# flipdot.net
KiCad netlist of a schematic drawn in Altium Designer
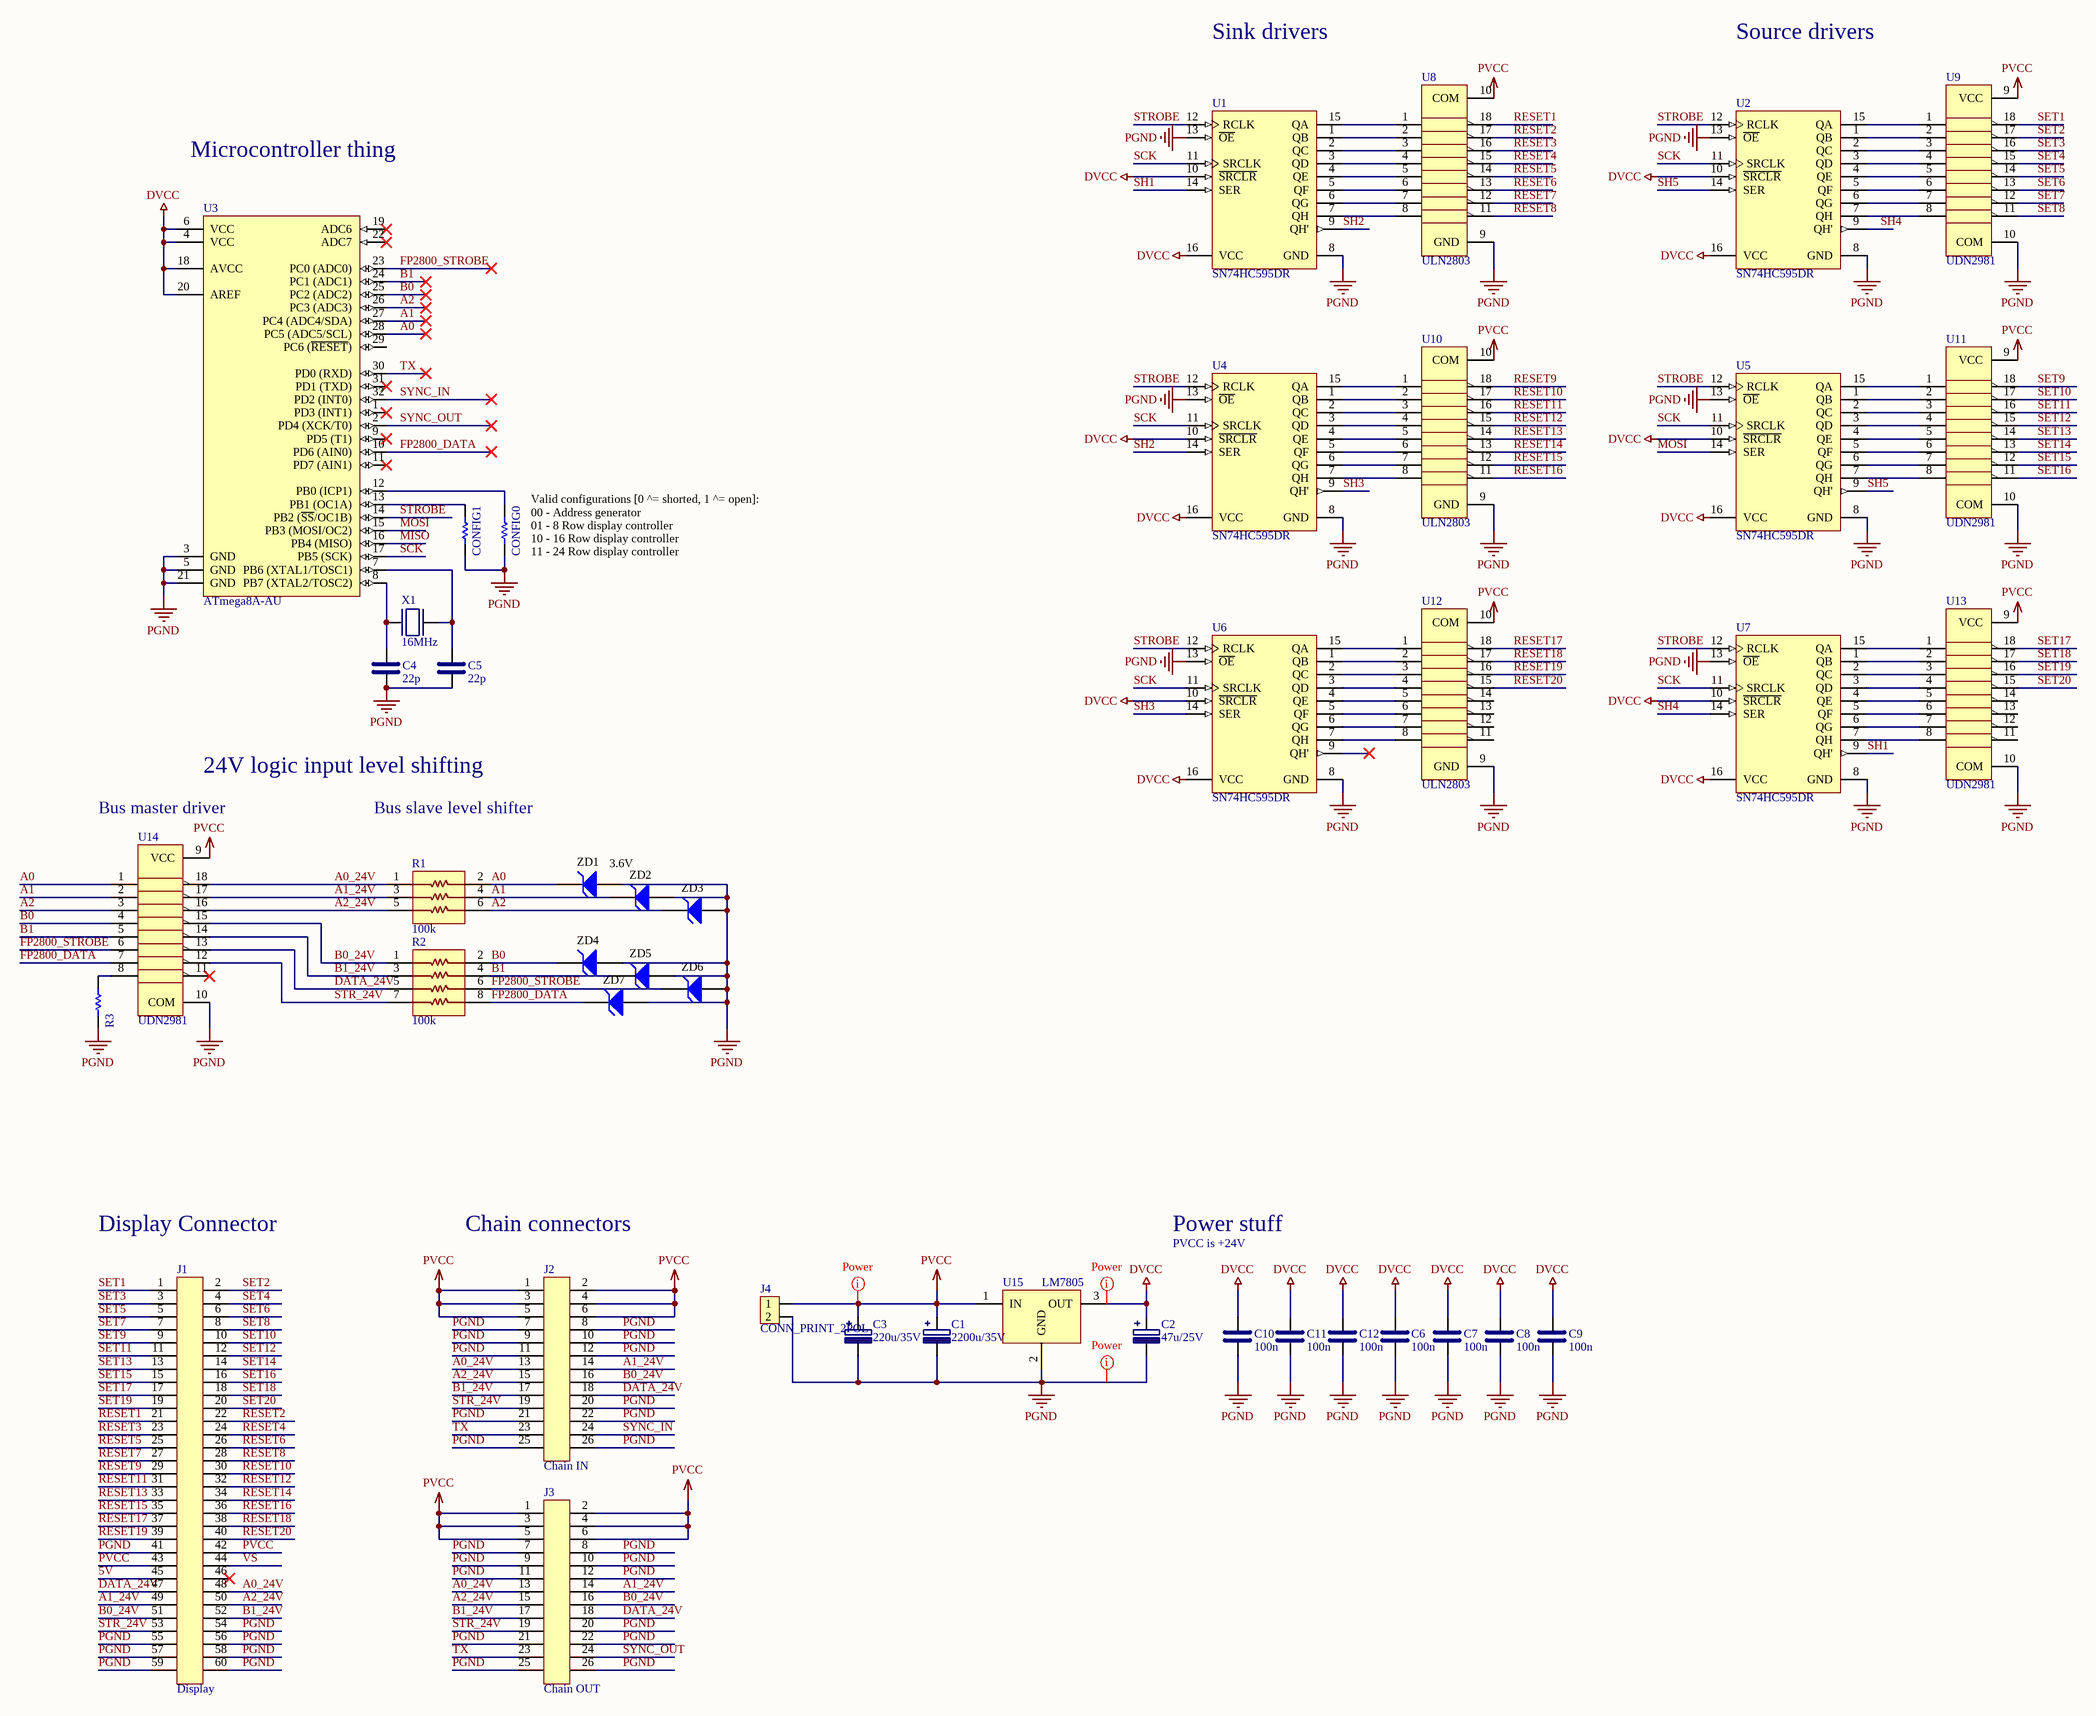
[diagram p0: flipdot.SchDoc]

(export (version "E")
  (design (tool "Eeschema 10.0.6"))
  (components
    (comp (ref "C1")
      (value "2200u/35V")
      (footprint "ELKO_RAD_SIDE_RM7.5_16x25")
      (description "Electrolytic Capacitor")
      (libsource (lib "flipdot") (part "CP"))
    )
    (comp (ref "C2")
      (value "47u/25V")
      (footprint "ELKO_RAD_RM2.0_dia5.0")
      (description "Electrolytic Capacitor")
      (libsource (lib "flipdot") (part "CP"))
    )
    (comp (ref "C3")
      (value "220u/35V")
      (footprint "ELKO_RAD_RM3.5_dia8.0")
      (description "Electrolytic Capacitor")
      (libsource (lib "flipdot") (part "CP"))
    )
    (comp (ref "C4")
      (value "22p")
      (footprint "6-0805_M")
      (description "Ceramic Capacitor")
      (libsource (lib "flipdot") (part "CCer"))
    )
    (comp (ref "C5")
      (value "22p")
      (footprint "6-0805_M")
      (description "Ceramic Capacitor")
      (libsource (lib "flipdot") (part "CCer"))
    )
    (comp (ref "C6")
      (value "100n")
      (footprint "6-0805_M")
      (description "Ceramic Capacitor")
      (libsource (lib "flipdot") (part "CCer"))
    )
    (comp (ref "C7")
      (value "100n")
      (footprint "6-0805_M")
      (description "Ceramic Capacitor")
      (libsource (lib "flipdot") (part "CCer"))
    )
    (comp (ref "C8")
      (value "100n")
      (footprint "6-0805_M")
      (description "Ceramic Capacitor")
      (libsource (lib "flipdot") (part "CCer"))
    )
    (comp (ref "C9")
      (value "100n")
      (footprint "6-0805_M")
      (description "Ceramic Capacitor")
      (libsource (lib "flipdot") (part "CCer"))
    )
    (comp (ref "C10")
      (value "100n")
      (footprint "6-0805_M")
      (description "Ceramic Capacitor")
      (libsource (lib "flipdot") (part "CCer"))
    )
    (comp (ref "C11")
      (value "100n")
      (footprint "6-0805_M")
      (description "Ceramic Capacitor")
      (libsource (lib "flipdot") (part "CCer"))
    )
    (comp (ref "C12")
      (value "100n")
      (footprint "6-0805_M")
      (description "Ceramic Capacitor")
      (libsource (lib "flipdot") (part "CCer"))
    )
    (comp (ref "CONFIG0")
      (value "Jumper 0603(1608)")
      (footprint "RESC0603(1608)_N")
      (description "Jumper 0603 (1608 Metric)")
      (fields (field (name "POWER") "None"))
      (libsource (lib "Altium Content Vault") (part "RES"))
    )
    (comp (ref "CONFIG1")
      (value "Jumper 0603(1608)")
      (footprint "RESC0603(1608)_N")
      (description "Jumper 0603 (1608 Metric)")
      (fields (field (name "POWER") "None"))
      (libsource (lib "Altium Content Vault") (part "RES"))
    )
    (comp (ref "J1")
      (value "Display")
      (footprint "PINHD_2x30_100mil")
      (libsource (lib "flipdot") (part "PINHD_2x30"))
    )
    (comp (ref "J2")
      (value "Chain IN")
      (footprint "PINHD_2x13_100mil")
      (libsource (lib "flipdot") (part "PINHD_2x13"))
    )
    (comp (ref "J3")
      (value "Chain OUT")
      (footprint "PINHD_2x13_100mil")
      (libsource (lib "flipdot") (part "PINHD_2x13"))
    )
    (comp (ref "J4")
      (value "CONN_PRINT_2POL")
      (footprint "CONN_PLUG_2P_5.08")
      (libsource (lib "flipdot") (part "CONN_PRINT_2POL"))
    )
    (comp (ref "R1")
      (value "100k")
      (footprint "RNET_SIL_100mil_6P")
      (description "6-pin Parallel Resistor Network")
      (libsource (lib "flipdot") (part "Rnet_Parallel_6"))
    )
    (comp (ref "R2")
      (value "100k")
      (footprint "RNET_SIL_100mil_8P")
      (description "8-pin Parallel Resistor Network")
      (libsource (lib "flipdot") (part "Rnet_Parallel_8"))
    )
    (comp (ref "R3")
      (value "Jumper 0603(1608)")
      (footprint "RESC0603(1608)_N")
      (description "Jumper 0603 (1608 Metric)")
      (fields (field (name "POWER") "None"))
      (libsource (lib "Altium Content Vault") (part "RES"))
    )
    (comp (ref "U1")
      (value "SN74HC595DR")
      (footprint "D0016A_M")
      (description "8-Bit Shift Registers With 3-State Output Registers, D0016A, LARGE T&R")
      (fields
        (field (name "GENERIC PART NUMBER") "SN74HC595")
        (field (name "MANUFACTURER") "Texas Instruments")
      )
      (libsource (lib "Altium Content Vault") (part "CMP-0780-00037-3"))
    )
    (comp (ref "U2")
      (value "SN74HC595DR")
      (footprint "D0016A_M")
      (description "8-Bit Shift Registers With 3-State Output Registers, D0016A, LARGE T&R")
      (fields
        (field (name "GENERIC PART NUMBER") "SN74HC595")
        (field (name "MANUFACTURER") "Texas Instruments")
      )
      (libsource (lib "Altium Content Vault") (part "CMP-0780-00037-3"))
    )
    (comp (ref "U3")
      (value "ATmega8A-AU")
      (footprint "32A_M")
      (libsource (lib "Altium Content Vault") (part "MC-8B-ATM8-SQ32"))
    )
    (comp (ref "U4")
      (value "SN74HC595DR")
      (footprint "D0016A_M")
      (description "8-Bit Shift Registers With 3-State Output Registers, D0016A, LARGE T&R")
      (fields
        (field (name "GENERIC PART NUMBER") "SN74HC595")
        (field (name "MANUFACTURER") "Texas Instruments")
      )
      (libsource (lib "Altium Content Vault") (part "CMP-0780-00037-3"))
    )
    (comp (ref "U5")
      (value "SN74HC595DR")
      (footprint "D0016A_M")
      (description "8-Bit Shift Registers With 3-State Output Registers, D0016A, LARGE T&R")
      (fields
        (field (name "GENERIC PART NUMBER") "SN74HC595")
        (field (name "MANUFACTURER") "Texas Instruments")
      )
      (libsource (lib "Altium Content Vault") (part "CMP-0780-00037-3"))
    )
    (comp (ref "U6")
      (value "SN74HC595DR")
      (footprint "D0016A_M")
      (description "8-Bit Shift Registers With 3-State Output Registers, D0016A, LARGE T&R")
      (fields
        (field (name "GENERIC PART NUMBER") "SN74HC595")
        (field (name "MANUFACTURER") "Texas Instruments")
      )
      (libsource (lib "Altium Content Vault") (part "CMP-0780-00037-3"))
    )
    (comp (ref "U7")
      (value "SN74HC595DR")
      (footprint "D0016A_M")
      (description "8-Bit Shift Registers With 3-State Output Registers, D0016A, LARGE T&R")
      (fields
        (field (name "GENERIC PART NUMBER") "SN74HC595")
        (field (name "MANUFACTURER") "Texas Instruments")
      )
      (libsource (lib "Altium Content Vault") (part "CMP-0780-00037-3"))
    )
    (comp (ref "U8")
      (value "ULN2803")
      (footprint "PDIP-18")
      (description "ULN2803 Octal Darlington Sink Driver")
      (libsource (lib "flipdot") (part "ULN2803"))
    )
    (comp (ref "U9")
      (value "UDN2981")
      (footprint "PDIP-18")
      (description "UDN2981 Octal Darlington Source Driver/Level Shifter")
      (libsource (lib "flipdot") (part "UDN2981"))
    )
    (comp (ref "U10")
      (value "ULN2803")
      (footprint "PDIP-18")
      (description "ULN2803 Octal Darlington Sink Driver")
      (libsource (lib "flipdot") (part "ULN2803"))
    )
    (comp (ref "U11")
      (value "UDN2981")
      (footprint "PDIP-18")
      (description "UDN2981 Octal Darlington Source Driver/Level Shifter")
      (libsource (lib "flipdot") (part "UDN2981"))
    )
    (comp (ref "U12")
      (value "ULN2803")
      (footprint "PDIP-18")
      (description "ULN2803 Octal Darlington Sink Driver")
      (libsource (lib "flipdot") (part "ULN2803"))
    )
    (comp (ref "U13")
      (value "UDN2981")
      (footprint "PDIP-18")
      (description "UDN2981 Octal Darlington Source Driver/Level Shifter")
      (libsource (lib "flipdot") (part "UDN2981"))
    )
    (comp (ref "U14")
      (value "UDN2981")
      (footprint "PDIP-18")
      (description "UDN2981 Octal Darlington Source Driver/Level Shifter")
      (libsource (lib "flipdot") (part "UDN2981"))
    )
    (comp (ref "U15")
      (value "LM7805")
      (footprint "TO92")
      (description "5V Linear Regulator")
      (libsource (lib "flipdot") (part "LM7805"))
    )
    (comp (ref "X1") (value "16MHz") (footprint "XTAL-HC49") (libsource (lib "flipdot") (part "XTAL")))
    (comp (ref "ZD1")
      (value "3.6V")
      (footprint "FAIR-DO-41-2_V")
      (description "Zener Diode, 5.6V, 1W, 5%, -65 to 200 degC, 2-Pin DO-41, Body 2.72 x 5.2 mm, RoHS")
      (fields (field (name "MANUFACTURER") "Fairchild Semiconductor") (field (name "TOLERANCE") "5%"))
      (libsource (lib "Altium Content Vault") (part "FAIR-DZEN-A1K2-2"))
    )
    (comp (ref "ZD2")
      (value "3.6V")
      (footprint "FAIR-DO-41-2_V")
      (description "Zener Diode, 5.6V, 1W, 5%, -65 to 200 degC, 2-Pin DO-41, Body 2.72 x 5.2 mm, RoHS")
      (fields (field (name "MANUFACTURER") "Fairchild Semiconductor") (field (name "TOLERANCE") "5%"))
      (libsource (lib "Altium Content Vault") (part "CMP-0892-00009-1"))
    )
    (comp (ref "ZD3")
      (value "3.6V")
      (footprint "FAIR-DO-41-2_V")
      (description "Zener Diode, 5.6V, 1W, 5%, -65 to 200 degC, 2-Pin DO-41, Body 2.72 x 5.2 mm, RoHS")
      (fields (field (name "MANUFACTURER") "Fairchild Semiconductor") (field (name "TOLERANCE") "5%"))
      (libsource (lib "Altium Content Vault") (part "CMP-0892-00009-1"))
    )
    (comp (ref "ZD4")
      (value "3.6V")
      (footprint "FAIR-DO-41-2_V")
      (description "Zener Diode, 5.6V, 1W, 5%, -65 to 200 degC, 2-Pin DO-41, Body 2.72 x 5.2 mm, RoHS")
      (fields (field (name "MANUFACTURER") "Fairchild Semiconductor") (field (name "TOLERANCE") "5%"))
      (libsource (lib "Altium Content Vault") (part "CMP-0892-00009-1"))
    )
    (comp (ref "ZD5")
      (value "3.6V")
      (footprint "FAIR-DO-41-2_V")
      (description "Zener Diode, 5.6V, 1W, 5%, -65 to 200 degC, 2-Pin DO-41, Body 2.72 x 5.2 mm, RoHS")
      (fields (field (name "MANUFACTURER") "Fairchild Semiconductor") (field (name "TOLERANCE") "5%"))
      (libsource (lib "Altium Content Vault") (part "CMP-0892-00009-1"))
    )
    (comp (ref "ZD6")
      (value "3.6V")
      (footprint "FAIR-DO-41-2_V")
      (description "Zener Diode, 5.6V, 1W, 5%, -65 to 200 degC, 2-Pin DO-41, Body 2.72 x 5.2 mm, RoHS")
      (fields (field (name "MANUFACTURER") "Fairchild Semiconductor") (field (name "TOLERANCE") "5%"))
      (libsource (lib "Altium Content Vault") (part "CMP-0892-00009-1"))
    )
    (comp (ref "ZD7")
      (value "3.6V")
      (footprint "FAIR-DO-41-2_V")
      (description "Zener Diode, 5.6V, 1W, 5%, -65 to 200 degC, 2-Pin DO-41, Body 2.72 x 5.2 mm, RoHS")
      (fields (field (name "MANUFACTURER") "Fairchild Semiconductor") (field (name "TOLERANCE") "5%"))
      (libsource (lib "Altium Content Vault") (part "CMP-0892-00009-1"))
    )
  )
  (nets
    (net (code "1") (name "/5V") (class "Default")
      (node (ref "J1") (pin "45") (pinfunction "45_45") (pintype "power_in"))
    )
    (net (code "2") (name "/A0") (class "Default")
      (node (ref "R1") (pin "2") (pintype "power_in"))
      (node (ref "U14") (pin "1") (pinfunction "IN1_1") (pintype "passive"))
      (node (ref "U3") (pin "28") (pinfunction "PC5_(ADC5/SCL)_28") (pintype "bidirectional"))
      (node (ref "ZD1") (pin "2") (pinfunction "K_2") (pintype "passive"))
    )
    (net (code "3") (name "/A0_24V") (class "Default")
      (node (ref "J1") (pin "48") (pinfunction "48_48") (pintype "power_in"))
      (node (ref "J2") (pin "13") (pinfunction "13_13") (pintype "power_in"))
      (node (ref "J3") (pin "13") (pinfunction "13_13") (pintype "power_in"))
      (node (ref "R1") (pin "1") (pinfunction "COM_1") (pintype "power_in"))
      (node (ref "U14") (pin "18") (pinfunction "OUT1_18") (pintype "passive"))
    )
    (net (code "4") (name "/A1") (class "Default")
      (node (ref "R1") (pin "4") (pintype "power_in"))
      (node (ref "U14") (pin "2") (pinfunction "IN2_2") (pintype "passive"))
      (node (ref "U3") (pin "27") (pinfunction "PC4_(ADC4/SDA)_27") (pintype "bidirectional"))
      (node (ref "ZD2") (pin "2") (pinfunction "K_2") (pintype "passive"))
    )
    (net (code "5") (name "/A1_24V") (class "Default")
      (node (ref "J1") (pin "49") (pinfunction "49_49") (pintype "power_in"))
      (node (ref "J2") (pin "14") (pinfunction "14_14") (pintype "power_in"))
      (node (ref "J3") (pin "14") (pinfunction "14_14") (pintype "power_in"))
      (node (ref "R1") (pin "3") (pintype "power_in"))
      (node (ref "U14") (pin "17") (pinfunction "OUT2_17") (pintype "passive"))
    )
    (net (code "6") (name "/A2") (class "Default")
      (node (ref "R1") (pin "6") (pintype "power_in"))
      (node (ref "U14") (pin "3") (pinfunction "IN3_3") (pintype "passive"))
      (node (ref "U3") (pin "26") (pinfunction "PC3_(ADC3)_26") (pintype "bidirectional"))
      (node (ref "ZD3") (pin "2") (pinfunction "K_2") (pintype "passive"))
    )
    (net (code "7") (name "/A2_24V") (class "Default")
      (node (ref "J1") (pin "50") (pinfunction "50_50") (pintype "power_in"))
      (node (ref "J2") (pin "15") (pinfunction "15_15") (pintype "power_in"))
      (node (ref "J3") (pin "15") (pinfunction "15_15") (pintype "power_in"))
      (node (ref "R1") (pin "5") (pintype "power_in"))
      (node (ref "U14") (pin "16") (pinfunction "OUT3_16") (pintype "passive"))
    )
    (net (code "8") (name "/B0") (class "Default")
      (node (ref "R2") (pin "2") (pintype "power_in"))
      (node (ref "U14") (pin "4") (pinfunction "IN4_4") (pintype "passive"))
      (node (ref "U3") (pin "25") (pinfunction "PC2_(ADC2)_25") (pintype "bidirectional"))
      (node (ref "ZD4") (pin "2") (pinfunction "K_2") (pintype "passive"))
    )
    (net (code "9") (name "/B0_24V") (class "Default")
      (node (ref "J1") (pin "51") (pinfunction "51_51") (pintype "power_in"))
      (node (ref "J2") (pin "16") (pinfunction "16_16") (pintype "power_in"))
      (node (ref "J3") (pin "16") (pinfunction "16_16") (pintype "power_in"))
      (node (ref "R2") (pin "1") (pinfunction "COM_1") (pintype "power_in"))
      (node (ref "U14") (pin "15") (pinfunction "OUT4_15") (pintype "passive"))
    )
    (net (code "10") (name "/B1") (class "Default")
      (node (ref "R2") (pin "4") (pintype "power_in"))
      (node (ref "U14") (pin "5") (pinfunction "IN5_5") (pintype "passive"))
      (node (ref "U3") (pin "24") (pinfunction "PC1_(ADC1)_24") (pintype "bidirectional"))
      (node (ref "ZD5") (pin "2") (pinfunction "K_2") (pintype "passive"))
    )
    (net (code "11") (name "/B1_24V") (class "Default")
      (node (ref "J1") (pin "52") (pinfunction "52_52") (pintype "power_in"))
      (node (ref "J2") (pin "17") (pinfunction "17_17") (pintype "power_in"))
      (node (ref "J3") (pin "17") (pinfunction "17_17") (pintype "power_in"))
      (node (ref "R2") (pin "3") (pintype "power_in"))
      (node (ref "U14") (pin "14") (pinfunction "OUT5_14") (pintype "passive"))
    )
    (net (code "12") (name "/DATA_24V") (class "Default")
      (node (ref "J1") (pin "47") (pinfunction "47_47") (pintype "power_in"))
      (node (ref "J2") (pin "18") (pinfunction "18_18") (pintype "power_in"))
      (node (ref "J3") (pin "18") (pinfunction "18_18") (pintype "power_in"))
      (node (ref "R2") (pin "5") (pintype "power_in"))
      (node (ref "U14") (pin "13") (pinfunction "OUT6_13") (pintype "passive"))
    )
    (net (code "13") (name "/FP2800_DATA") (class "Default")
      (node (ref "R2") (pin "8") (pintype "power_in"))
      (node (ref "U14") (pin "7") (pinfunction "IN7_7") (pintype "passive"))
      (node (ref "U3") (pin "10") (pinfunction "PD6_(AIN0)_10") (pintype "bidirectional"))
      (node (ref "ZD7") (pin "2") (pinfunction "K_2") (pintype "passive"))
    )
    (net (code "14") (name "/FP2800_STROBE") (class "Default")
      (node (ref "R2") (pin "6") (pintype "power_in"))
      (node (ref "U14") (pin "6") (pinfunction "IN6_6") (pintype "passive"))
      (node (ref "U3") (pin "23") (pinfunction "PC0_(ADC0)_23") (pintype "bidirectional"))
      (node (ref "ZD6") (pin "2") (pinfunction "K_2") (pintype "passive"))
    )
    (net (code "15") (name "/MISO") (class "Default")
      (node (ref "U3") (pin "16") (pinfunction "PB4_(MISO)_16") (pintype "bidirectional"))
    )
    (net (code "16") (name "/MOSI") (class "Default")
      (node (ref "U3") (pin "15") (pinfunction "PB3_(MOSI/OC2)_15") (pintype "bidirectional"))
      (node (ref "U5") (pin "14") (pinfunction "SER_14") (pintype "input"))
    )
    (net (code "17") (name "/RESET1") (class "Default")
      (node (ref "J1") (pin "21") (pinfunction "21_21") (pintype "power_in"))
      (node (ref "U8") (pin "18") (pinfunction "OUT1_18") (pintype "passive"))
    )
    (net (code "18") (name "/RESET2") (class "Default")
      (node (ref "J1") (pin "22") (pinfunction "22_22") (pintype "power_in"))
      (node (ref "U8") (pin "17") (pinfunction "OUT2_17") (pintype "passive"))
    )
    (net (code "19") (name "/RESET3") (class "Default")
      (node (ref "J1") (pin "23") (pinfunction "23_23") (pintype "power_in"))
      (node (ref "U8") (pin "16") (pinfunction "OUT3_16") (pintype "passive"))
    )
    (net (code "20") (name "/RESET4") (class "Default")
      (node (ref "J1") (pin "24") (pinfunction "24_24") (pintype "power_in"))
      (node (ref "U8") (pin "15") (pinfunction "OUT4_15") (pintype "passive"))
    )
    (net (code "21") (name "/RESET5") (class "Default")
      (node (ref "J1") (pin "25") (pinfunction "25_25") (pintype "power_in"))
      (node (ref "U8") (pin "14") (pinfunction "OUT5_14") (pintype "passive"))
    )
    (net (code "22") (name "/RESET6") (class "Default")
      (node (ref "J1") (pin "26") (pinfunction "26_26") (pintype "power_in"))
      (node (ref "U8") (pin "13") (pinfunction "OUT6_13") (pintype "passive"))
    )
    (net (code "23") (name "/RESET7") (class "Default")
      (node (ref "J1") (pin "27") (pinfunction "27_27") (pintype "power_in"))
      (node (ref "U8") (pin "12") (pinfunction "OUT7_12") (pintype "passive"))
    )
    (net (code "24") (name "/RESET8") (class "Default")
      (node (ref "J1") (pin "28") (pinfunction "28_28") (pintype "power_in"))
      (node (ref "U8") (pin "11") (pinfunction "OUT8_11") (pintype "passive"))
    )
    (net (code "25") (name "/RESET9") (class "Default")
      (node (ref "J1") (pin "29") (pinfunction "29_29") (pintype "power_in"))
      (node (ref "U10") (pin "18") (pinfunction "OUT1_18") (pintype "passive"))
    )
    (net (code "26") (name "/RESET10") (class "Default")
      (node (ref "J1") (pin "30") (pinfunction "30_30") (pintype "power_in"))
      (node (ref "U10") (pin "17") (pinfunction "OUT2_17") (pintype "passive"))
    )
    (net (code "27") (name "/RESET11") (class "Default")
      (node (ref "J1") (pin "31") (pinfunction "31_31") (pintype "power_in"))
      (node (ref "U10") (pin "16") (pinfunction "OUT3_16") (pintype "passive"))
    )
    (net (code "28") (name "/RESET12") (class "Default")
      (node (ref "J1") (pin "32") (pinfunction "32_32") (pintype "power_in"))
      (node (ref "U10") (pin "15") (pinfunction "OUT4_15") (pintype "passive"))
    )
    (net (code "29") (name "/RESET13") (class "Default")
      (node (ref "J1") (pin "33") (pinfunction "33_33") (pintype "power_in"))
      (node (ref "U10") (pin "14") (pinfunction "OUT5_14") (pintype "passive"))
    )
    (net (code "30") (name "/RESET14") (class "Default")
      (node (ref "J1") (pin "34") (pinfunction "34_34") (pintype "power_in"))
      (node (ref "U10") (pin "13") (pinfunction "OUT6_13") (pintype "passive"))
    )
    (net (code "31") (name "/RESET15") (class "Default")
      (node (ref "J1") (pin "35") (pinfunction "35_35") (pintype "power_in"))
      (node (ref "U10") (pin "12") (pinfunction "OUT7_12") (pintype "passive"))
    )
    (net (code "32") (name "/RESET16") (class "Default")
      (node (ref "J1") (pin "36") (pinfunction "36_36") (pintype "power_in"))
      (node (ref "U10") (pin "11") (pinfunction "OUT8_11") (pintype "passive"))
    )
    (net (code "33") (name "/RESET17") (class "Default")
      (node (ref "J1") (pin "37") (pinfunction "37_37") (pintype "power_in"))
      (node (ref "U12") (pin "18") (pinfunction "OUT1_18") (pintype "passive"))
    )
    (net (code "34") (name "/RESET18") (class "Default")
      (node (ref "J1") (pin "38") (pinfunction "38_38") (pintype "power_in"))
      (node (ref "U12") (pin "17") (pinfunction "OUT2_17") (pintype "passive"))
    )
    (net (code "35") (name "/RESET19") (class "Default")
      (node (ref "J1") (pin "39") (pinfunction "39_39") (pintype "power_in"))
      (node (ref "U12") (pin "16") (pinfunction "OUT3_16") (pintype "passive"))
    )
    (net (code "36") (name "/RESET20") (class "Default")
      (node (ref "J1") (pin "40") (pinfunction "40_40") (pintype "power_in"))
      (node (ref "U12") (pin "15") (pinfunction "OUT4_15") (pintype "passive"))
    )
    (net (code "37") (name "/SCK") (class "Default")
      (node (ref "U1") (pin "11") (pinfunction "SRCLK_11") (pintype "input"))
      (node (ref "U2") (pin "11") (pinfunction "SRCLK_11") (pintype "input"))
      (node (ref "U3") (pin "17") (pinfunction "PB5_(SCK)_17") (pintype "bidirectional"))
      (node (ref "U4") (pin "11") (pinfunction "SRCLK_11") (pintype "input"))
      (node (ref "U5") (pin "11") (pinfunction "SRCLK_11") (pintype "input"))
      (node (ref "U6") (pin "11") (pinfunction "SRCLK_11") (pintype "input"))
      (node (ref "U7") (pin "11") (pinfunction "SRCLK_11") (pintype "input"))
    )
    (net (code "38") (name "/SET1") (class "Default")
      (node (ref "J1") (pin "1") (pinfunction "1_1") (pintype "power_in"))
      (node (ref "U9") (pin "18") (pinfunction "OUT1_18") (pintype "passive"))
    )
    (net (code "39") (name "/SET2") (class "Default")
      (node (ref "J1") (pin "2") (pinfunction "2_2") (pintype "power_in"))
      (node (ref "U9") (pin "17") (pinfunction "OUT2_17") (pintype "passive"))
    )
    (net (code "40") (name "/SET3") (class "Default")
      (node (ref "J1") (pin "3") (pinfunction "3_3") (pintype "power_in"))
      (node (ref "U9") (pin "16") (pinfunction "OUT3_16") (pintype "passive"))
    )
    (net (code "41") (name "/SET4") (class "Default")
      (node (ref "J1") (pin "4") (pinfunction "4_4") (pintype "power_in"))
      (node (ref "U9") (pin "15") (pinfunction "OUT4_15") (pintype "passive"))
    )
    (net (code "42") (name "/SET5") (class "Default")
      (node (ref "J1") (pin "5") (pinfunction "5_5") (pintype "power_in"))
      (node (ref "U9") (pin "14") (pinfunction "OUT5_14") (pintype "passive"))
    )
    (net (code "43") (name "/SET6") (class "Default")
      (node (ref "J1") (pin "6") (pinfunction "6_6") (pintype "power_in"))
      (node (ref "U9") (pin "13") (pinfunction "OUT6_13") (pintype "passive"))
    )
    (net (code "44") (name "/SET7") (class "Default")
      (node (ref "J1") (pin "7") (pinfunction "7_7") (pintype "power_in"))
      (node (ref "U9") (pin "12") (pinfunction "OUT7_12") (pintype "passive"))
    )
    (net (code "45") (name "/SET8") (class "Default")
      (node (ref "J1") (pin "8") (pinfunction "8_8") (pintype "power_in"))
      (node (ref "U9") (pin "11") (pinfunction "OUT8_11") (pintype "passive"))
    )
    (net (code "46") (name "/SET9") (class "Default")
      (node (ref "J1") (pin "9") (pinfunction "9_9") (pintype "power_in"))
      (node (ref "U11") (pin "18") (pinfunction "OUT1_18") (pintype "passive"))
    )
    (net (code "47") (name "/SET10") (class "Default")
      (node (ref "J1") (pin "10") (pinfunction "10_10") (pintype "power_in"))
      (node (ref "U11") (pin "17") (pinfunction "OUT2_17") (pintype "passive"))
    )
    (net (code "48") (name "/SET11") (class "Default")
      (node (ref "J1") (pin "11") (pinfunction "11_11") (pintype "power_in"))
      (node (ref "U11") (pin "16") (pinfunction "OUT3_16") (pintype "passive"))
    )
    (net (code "49") (name "/SET12") (class "Default")
      (node (ref "J1") (pin "12") (pinfunction "12_12") (pintype "power_in"))
      (node (ref "U11") (pin "15") (pinfunction "OUT4_15") (pintype "passive"))
    )
    (net (code "50") (name "/SET13") (class "Default")
      (node (ref "J1") (pin "13") (pinfunction "13_13") (pintype "power_in"))
      (node (ref "U11") (pin "14") (pinfunction "OUT5_14") (pintype "passive"))
    )
    (net (code "51") (name "/SET14") (class "Default")
      (node (ref "J1") (pin "14") (pinfunction "14_14") (pintype "power_in"))
      (node (ref "U11") (pin "13") (pinfunction "OUT6_13") (pintype "passive"))
    )
    (net (code "52") (name "/SET15") (class "Default")
      (node (ref "J1") (pin "15") (pinfunction "15_15") (pintype "power_in"))
      (node (ref "U11") (pin "12") (pinfunction "OUT7_12") (pintype "passive"))
    )
    (net (code "53") (name "/SET16") (class "Default")
      (node (ref "J1") (pin "16") (pinfunction "16_16") (pintype "power_in"))
      (node (ref "U11") (pin "11") (pinfunction "OUT8_11") (pintype "passive"))
    )
    (net (code "54") (name "/SET17") (class "Default")
      (node (ref "J1") (pin "17") (pinfunction "17_17") (pintype "power_in"))
      (node (ref "U13") (pin "18") (pinfunction "OUT1_18") (pintype "passive"))
    )
    (net (code "55") (name "/SET18") (class "Default")
      (node (ref "J1") (pin "18") (pinfunction "18_18") (pintype "power_in"))
      (node (ref "U13") (pin "17") (pinfunction "OUT2_17") (pintype "passive"))
    )
    (net (code "56") (name "/SET19") (class "Default")
      (node (ref "J1") (pin "19") (pinfunction "19_19") (pintype "power_in"))
      (node (ref "U13") (pin "16") (pinfunction "OUT3_16") (pintype "passive"))
    )
    (net (code "57") (name "/SET20") (class "Default")
      (node (ref "J1") (pin "20") (pinfunction "20_20") (pintype "power_in"))
      (node (ref "U13") (pin "15") (pinfunction "OUT4_15") (pintype "passive"))
    )
    (net (code "58") (name "/SH1") (class "Default")
      (node (ref "U1") (pin "14") (pinfunction "SER_14") (pintype "input"))
      (node (ref "U7") (pin "9") (pinfunction "QH'_9") (pintype "output"))
    )
    (net (code "59") (name "/SH2") (class "Default")
      (node (ref "U1") (pin "9") (pinfunction "QH'_9") (pintype "output"))
      (node (ref "U4") (pin "14") (pinfunction "SER_14") (pintype "input"))
    )
    (net (code "60") (name "/SH3") (class "Default")
      (node (ref "U4") (pin "9") (pinfunction "QH'_9") (pintype "output"))
      (node (ref "U6") (pin "14") (pinfunction "SER_14") (pintype "input"))
    )
    (net (code "61") (name "/SH4") (class "Default")
      (node (ref "U2") (pin "9") (pinfunction "QH'_9") (pintype "output"))
      (node (ref "U7") (pin "14") (pinfunction "SER_14") (pintype "input"))
    )
    (net (code "62") (name "/SH5") (class "Default")
      (node (ref "U2") (pin "14") (pinfunction "SER_14") (pintype "input"))
      (node (ref "U5") (pin "9") (pinfunction "QH'_9") (pintype "output"))
    )
    (net (code "63") (name "/STROBE") (class "Default")
      (node (ref "U1") (pin "12") (pinfunction "RCLK_12") (pintype "input"))
      (node (ref "U2") (pin "12") (pinfunction "RCLK_12") (pintype "input"))
      (node (ref "U3") (pin "14") (pinfunction "PB2_(~{SS}/OC1B)_14") (pintype "bidirectional"))
      (node (ref "U4") (pin "12") (pinfunction "RCLK_12") (pintype "input"))
      (node (ref "U5") (pin "12") (pinfunction "RCLK_12") (pintype "input"))
      (node (ref "U6") (pin "12") (pinfunction "RCLK_12") (pintype "input"))
      (node (ref "U7") (pin "12") (pinfunction "RCLK_12") (pintype "input"))
    )
    (net (code "64") (name "/STR_24V") (class "Default")
      (node (ref "J1") (pin "53") (pinfunction "53_53") (pintype "power_in"))
      (node (ref "J2") (pin "19") (pinfunction "19_19") (pintype "power_in"))
      (node (ref "J3") (pin "19") (pinfunction "19_19") (pintype "power_in"))
      (node (ref "R2") (pin "7") (pintype "power_in"))
      (node (ref "U14") (pin "12") (pinfunction "OUT7_12") (pintype "passive"))
    )
    (net (code "65") (name "/SYNC_IN") (class "Default")
      (node (ref "J2") (pin "24") (pinfunction "24_24") (pintype "power_in"))
      (node (ref "U3") (pin "32") (pinfunction "PD2_(INT0)_32") (pintype "bidirectional"))
    )
    (net (code "66") (name "/SYNC_OUT") (class "Default")
      (node (ref "J3") (pin "24") (pinfunction "24_24") (pintype "power_in"))
      (node (ref "U3") (pin "2") (pinfunction "PD4_(XCK/T0)_2") (pintype "bidirectional"))
    )
    (net (code "67") (name "/TX") (class "Default")
      (node (ref "J2") (pin "23") (pinfunction "23_23") (pintype "power_in"))
      (node (ref "J3") (pin "23") (pinfunction "23_23") (pintype "power_in"))
      (node (ref "U3") (pin "30") (pinfunction "PD0_(RXD)_30") (pintype "bidirectional"))
    )
    (net (code "68") (name "/VS") (class "Default")
      (node (ref "J1") (pin "44") (pinfunction "44_44") (pintype "power_in"))
    )
    (net (code "69") (name "DVCC") (class "Default")
      (node (ref "C10") (pin "1") (pinfunction "+_1") (pintype "passive"))
      (node (ref "C11") (pin "1") (pinfunction "+_1") (pintype "passive"))
      (node (ref "C12") (pin "1") (pinfunction "+_1") (pintype "passive"))
      (node (ref "C2") (pin "P") (pinfunction "+_P") (pintype "passive"))
      (node (ref "C6") (pin "1") (pinfunction "+_1") (pintype "passive"))
      (node (ref "C7") (pin "1") (pinfunction "+_1") (pintype "passive"))
      (node (ref "C8") (pin "1") (pinfunction "+_1") (pintype "passive"))
      (node (ref "C9") (pin "1") (pinfunction "+_1") (pintype "passive"))
      (node (ref "U1") (pin "10") (pinfunction "~{SRCLR}_10") (pintype "input"))
      (node (ref "U1") (pin "16") (pinfunction "VCC_16") (pintype "power_in"))
      (node (ref "U15") (pin "3") (pinfunction "OUT_3") (pintype "passive"))
      (node (ref "U2") (pin "10") (pinfunction "~{SRCLR}_10") (pintype "input"))
      (node (ref "U2") (pin "16") (pinfunction "VCC_16") (pintype "power_in"))
      (node (ref "U3") (pin "18") (pinfunction "AVCC_18") (pintype "power_in"))
      (node (ref "U3") (pin "20") (pinfunction "AREF_20") (pintype "power_in"))
      (node (ref "U3") (pin "4") (pinfunction "VCC_4") (pintype "power_in"))
      (node (ref "U3") (pin "6") (pinfunction "VCC_6") (pintype "power_in"))
      (node (ref "U4") (pin "10") (pinfunction "~{SRCLR}_10") (pintype "input"))
      (node (ref "U4") (pin "16") (pinfunction "VCC_16") (pintype "power_in"))
      (node (ref "U5") (pin "10") (pinfunction "~{SRCLR}_10") (pintype "input"))
      (node (ref "U5") (pin "16") (pinfunction "VCC_16") (pintype "power_in"))
      (node (ref "U6") (pin "10") (pinfunction "~{SRCLR}_10") (pintype "input"))
      (node (ref "U6") (pin "16") (pinfunction "VCC_16") (pintype "power_in"))
      (node (ref "U7") (pin "10") (pinfunction "~{SRCLR}_10") (pintype "input"))
      (node (ref "U7") (pin "16") (pinfunction "VCC_16") (pintype "power_in"))
    )
    (net (code "70") (name "Net-(C4-+)") (class "Default")
      (node (ref "C4") (pin "1") (pinfunction "+_1") (pintype "passive"))
      (node (ref "U3") (pin "8") (pinfunction "PB7_(XTAL2/TOSC2)_8") (pintype "bidirectional"))
      (node (ref "X1") (pin "1") (pinfunction "1_1") (pintype "passive"))
    )
    (net (code "71") (name "Net-(C5-+)") (class "Default")
      (node (ref "C5") (pin "1") (pinfunction "+_1") (pintype "passive"))
      (node (ref "U3") (pin "7") (pinfunction "PB6_(XTAL1/TOSC1)_7") (pintype "bidirectional"))
      (node (ref "X1") (pin "2") (pinfunction "2_2") (pintype "passive"))
    )
    (net (code "72") (name "Net-(U1-QA)") (class "Default")
      (node (ref "U1") (pin "15") (pinfunction "QA_15") (pintype "tri_state"))
      (node (ref "U8") (pin "1") (pinfunction "IN1_1") (pintype "passive"))
    )
    (net (code "73") (name "Net-(U1-QB)") (class "Default")
      (node (ref "U1") (pin "1") (pinfunction "QB_1") (pintype "tri_state"))
      (node (ref "U8") (pin "2") (pinfunction "IN2_2") (pintype "passive"))
    )
    (net (code "74") (name "Net-(U1-QC)") (class "Default")
      (node (ref "U1") (pin "2") (pinfunction "QC_2") (pintype "tri_state"))
      (node (ref "U8") (pin "3") (pinfunction "IN3_3") (pintype "passive"))
    )
    (net (code "75") (name "Net-(U1-QD)") (class "Default")
      (node (ref "U1") (pin "3") (pinfunction "QD_3") (pintype "tri_state"))
      (node (ref "U8") (pin "4") (pinfunction "IN4_4") (pintype "passive"))
    )
    (net (code "76") (name "Net-(U1-QE)") (class "Default")
      (node (ref "U1") (pin "4") (pinfunction "QE_4") (pintype "tri_state"))
      (node (ref "U8") (pin "5") (pinfunction "IN5_5") (pintype "passive"))
    )
    (net (code "77") (name "Net-(U1-QF)") (class "Default")
      (node (ref "U1") (pin "5") (pinfunction "QF_5") (pintype "tri_state"))
      (node (ref "U8") (pin "6") (pinfunction "IN6_6") (pintype "passive"))
    )
    (net (code "78") (name "Net-(U1-QG)") (class "Default")
      (node (ref "U1") (pin "6") (pinfunction "QG_6") (pintype "tri_state"))
      (node (ref "U8") (pin "7") (pinfunction "IN7_7") (pintype "passive"))
    )
    (net (code "79") (name "Net-(U1-QH)") (class "Default")
      (node (ref "U1") (pin "7") (pinfunction "QH_7") (pintype "tri_state"))
      (node (ref "U8") (pin "8") (pinfunction "IN8_8") (pintype "passive"))
    )
    (net (code "80") (name "Net-(U2-QA)") (class "Default")
      (node (ref "U2") (pin "15") (pinfunction "QA_15") (pintype "tri_state"))
      (node (ref "U9") (pin "1") (pinfunction "IN1_1") (pintype "passive"))
    )
    (net (code "81") (name "Net-(U2-QB)") (class "Default")
      (node (ref "U2") (pin "1") (pinfunction "QB_1") (pintype "tri_state"))
      (node (ref "U9") (pin "2") (pinfunction "IN2_2") (pintype "passive"))
    )
    (net (code "82") (name "Net-(U2-QC)") (class "Default")
      (node (ref "U2") (pin "2") (pinfunction "QC_2") (pintype "tri_state"))
      (node (ref "U9") (pin "3") (pinfunction "IN3_3") (pintype "passive"))
    )
    (net (code "83") (name "Net-(U2-QD)") (class "Default")
      (node (ref "U2") (pin "3") (pinfunction "QD_3") (pintype "tri_state"))
      (node (ref "U9") (pin "4") (pinfunction "IN4_4") (pintype "passive"))
    )
    (net (code "84") (name "Net-(U2-QE)") (class "Default")
      (node (ref "U2") (pin "4") (pinfunction "QE_4") (pintype "tri_state"))
      (node (ref "U9") (pin "5") (pinfunction "IN5_5") (pintype "passive"))
    )
    (net (code "85") (name "Net-(U2-QF)") (class "Default")
      (node (ref "U2") (pin "5") (pinfunction "QF_5") (pintype "tri_state"))
      (node (ref "U9") (pin "6") (pinfunction "IN6_6") (pintype "passive"))
    )
    (net (code "86") (name "Net-(U2-QG)") (class "Default")
      (node (ref "U2") (pin "6") (pinfunction "QG_6") (pintype "tri_state"))
      (node (ref "U9") (pin "7") (pinfunction "IN7_7") (pintype "passive"))
    )
    (net (code "87") (name "Net-(U2-QH)") (class "Default")
      (node (ref "U2") (pin "7") (pinfunction "QH_7") (pintype "tri_state"))
      (node (ref "U9") (pin "8") (pinfunction "IN8_8") (pintype "passive"))
    )
    (net (code "88") (name "Net-(U3-PB0_(ICP1))") (class "Default")
      (node (ref "CONFIG0") (pin "1") (pinfunction "1_1") (pintype "passive"))
      (node (ref "U3") (pin "12") (pinfunction "PB0_(ICP1)_12") (pintype "bidirectional"))
    )
    (net (code "89") (name "Net-(U3-PB1_(OC1A))") (class "Default")
      (node (ref "CONFIG1") (pin "2") (pinfunction "2_2") (pintype "passive"))
      (node (ref "U3") (pin "13") (pinfunction "PB1_(OC1A)_13") (pintype "bidirectional"))
    )
    (net (code "90") (name "Net-(U10-IN1)") (class "Default")
      (node (ref "U10") (pin "1") (pinfunction "IN1_1") (pintype "passive"))
      (node (ref "U4") (pin "15") (pinfunction "QA_15") (pintype "tri_state"))
    )
    (net (code "91") (name "Net-(U10-IN2)") (class "Default")
      (node (ref "U10") (pin "2") (pinfunction "IN2_2") (pintype "passive"))
      (node (ref "U4") (pin "1") (pinfunction "QB_1") (pintype "tri_state"))
    )
    (net (code "92") (name "Net-(U10-IN3)") (class "Default")
      (node (ref "U10") (pin "3") (pinfunction "IN3_3") (pintype "passive"))
      (node (ref "U4") (pin "2") (pinfunction "QC_2") (pintype "tri_state"))
    )
    (net (code "93") (name "Net-(U10-IN4)") (class "Default")
      (node (ref "U10") (pin "4") (pinfunction "IN4_4") (pintype "passive"))
      (node (ref "U4") (pin "3") (pinfunction "QD_3") (pintype "tri_state"))
    )
    (net (code "94") (name "Net-(U10-IN5)") (class "Default")
      (node (ref "U10") (pin "5") (pinfunction "IN5_5") (pintype "passive"))
      (node (ref "U4") (pin "4") (pinfunction "QE_4") (pintype "tri_state"))
    )
    (net (code "95") (name "Net-(U10-IN6)") (class "Default")
      (node (ref "U10") (pin "6") (pinfunction "IN6_6") (pintype "passive"))
      (node (ref "U4") (pin "5") (pinfunction "QF_5") (pintype "tri_state"))
    )
    (net (code "96") (name "Net-(U10-IN7)") (class "Default")
      (node (ref "U10") (pin "7") (pinfunction "IN7_7") (pintype "passive"))
      (node (ref "U4") (pin "6") (pinfunction "QG_6") (pintype "tri_state"))
    )
    (net (code "97") (name "Net-(U10-IN8)") (class "Default")
      (node (ref "U10") (pin "8") (pinfunction "IN8_8") (pintype "passive"))
      (node (ref "U4") (pin "7") (pinfunction "QH_7") (pintype "tri_state"))
    )
    (net (code "98") (name "Net-(U11-IN1)") (class "Default")
      (node (ref "U11") (pin "1") (pinfunction "IN1_1") (pintype "passive"))
      (node (ref "U5") (pin "15") (pinfunction "QA_15") (pintype "tri_state"))
    )
    (net (code "99") (name "Net-(U11-IN2)") (class "Default")
      (node (ref "U11") (pin "2") (pinfunction "IN2_2") (pintype "passive"))
      (node (ref "U5") (pin "1") (pinfunction "QB_1") (pintype "tri_state"))
    )
    (net (code "100") (name "Net-(U11-IN3)") (class "Default")
      (node (ref "U11") (pin "3") (pinfunction "IN3_3") (pintype "passive"))
      (node (ref "U5") (pin "2") (pinfunction "QC_2") (pintype "tri_state"))
    )
    (net (code "101") (name "Net-(U11-IN4)") (class "Default")
      (node (ref "U11") (pin "4") (pinfunction "IN4_4") (pintype "passive"))
      (node (ref "U5") (pin "3") (pinfunction "QD_3") (pintype "tri_state"))
    )
    (net (code "102") (name "Net-(U11-IN5)") (class "Default")
      (node (ref "U11") (pin "5") (pinfunction "IN5_5") (pintype "passive"))
      (node (ref "U5") (pin "4") (pinfunction "QE_4") (pintype "tri_state"))
    )
    (net (code "103") (name "Net-(U11-IN6)") (class "Default")
      (node (ref "U11") (pin "6") (pinfunction "IN6_6") (pintype "passive"))
      (node (ref "U5") (pin "5") (pinfunction "QF_5") (pintype "tri_state"))
    )
    (net (code "104") (name "Net-(U11-IN7)") (class "Default")
      (node (ref "U11") (pin "7") (pinfunction "IN7_7") (pintype "passive"))
      (node (ref "U5") (pin "6") (pinfunction "QG_6") (pintype "tri_state"))
    )
    (net (code "105") (name "Net-(U11-IN8)") (class "Default")
      (node (ref "U11") (pin "8") (pinfunction "IN8_8") (pintype "passive"))
      (node (ref "U5") (pin "7") (pinfunction "QH_7") (pintype "tri_state"))
    )
    (net (code "106") (name "Net-(U12-IN1)") (class "Default")
      (node (ref "U12") (pin "1") (pinfunction "IN1_1") (pintype "passive"))
      (node (ref "U6") (pin "15") (pinfunction "QA_15") (pintype "tri_state"))
    )
    (net (code "107") (name "Net-(U12-IN2)") (class "Default")
      (node (ref "U12") (pin "2") (pinfunction "IN2_2") (pintype "passive"))
      (node (ref "U6") (pin "1") (pinfunction "QB_1") (pintype "tri_state"))
    )
    (net (code "108") (name "Net-(U12-IN3)") (class "Default")
      (node (ref "U12") (pin "3") (pinfunction "IN3_3") (pintype "passive"))
      (node (ref "U6") (pin "2") (pinfunction "QC_2") (pintype "tri_state"))
    )
    (net (code "109") (name "Net-(U12-IN4)") (class "Default")
      (node (ref "U12") (pin "4") (pinfunction "IN4_4") (pintype "passive"))
      (node (ref "U6") (pin "3") (pinfunction "QD_3") (pintype "tri_state"))
    )
    (net (code "110") (name "Net-(U12-IN5)") (class "Default")
      (node (ref "U12") (pin "5") (pinfunction "IN5_5") (pintype "passive"))
      (node (ref "U6") (pin "4") (pinfunction "QE_4") (pintype "tri_state"))
    )
    (net (code "111") (name "Net-(U12-IN6)") (class "Default")
      (node (ref "U12") (pin "6") (pinfunction "IN6_6") (pintype "passive"))
      (node (ref "U6") (pin "5") (pinfunction "QF_5") (pintype "tri_state"))
    )
    (net (code "112") (name "Net-(U12-IN7)") (class "Default")
      (node (ref "U12") (pin "7") (pinfunction "IN7_7") (pintype "passive"))
      (node (ref "U6") (pin "6") (pinfunction "QG_6") (pintype "tri_state"))
    )
    (net (code "113") (name "Net-(U12-IN8)") (class "Default")
      (node (ref "U12") (pin "8") (pinfunction "IN8_8") (pintype "passive"))
      (node (ref "U6") (pin "7") (pinfunction "QH_7") (pintype "tri_state"))
    )
    (net (code "114") (name "Net-(U13-IN1)") (class "Default")
      (node (ref "U13") (pin "1") (pinfunction "IN1_1") (pintype "passive"))
      (node (ref "U7") (pin "15") (pinfunction "QA_15") (pintype "tri_state"))
    )
    (net (code "115") (name "Net-(U13-IN2)") (class "Default")
      (node (ref "U13") (pin "2") (pinfunction "IN2_2") (pintype "passive"))
      (node (ref "U7") (pin "1") (pinfunction "QB_1") (pintype "tri_state"))
    )
    (net (code "116") (name "Net-(U13-IN3)") (class "Default")
      (node (ref "U13") (pin "3") (pinfunction "IN3_3") (pintype "passive"))
      (node (ref "U7") (pin "2") (pinfunction "QC_2") (pintype "tri_state"))
    )
    (net (code "117") (name "Net-(U13-IN4)") (class "Default")
      (node (ref "U13") (pin "4") (pinfunction "IN4_4") (pintype "passive"))
      (node (ref "U7") (pin "3") (pinfunction "QD_3") (pintype "tri_state"))
    )
    (net (code "118") (name "Net-(U13-IN5)") (class "Default")
      (node (ref "U13") (pin "5") (pinfunction "IN5_5") (pintype "passive"))
      (node (ref "U7") (pin "4") (pinfunction "QE_4") (pintype "tri_state"))
    )
    (net (code "119") (name "Net-(U13-IN6)") (class "Default")
      (node (ref "U13") (pin "6") (pinfunction "IN6_6") (pintype "passive"))
      (node (ref "U7") (pin "5") (pinfunction "QF_5") (pintype "tri_state"))
    )
    (net (code "120") (name "Net-(U13-IN7)") (class "Default")
      (node (ref "U13") (pin "7") (pinfunction "IN7_7") (pintype "passive"))
      (node (ref "U7") (pin "6") (pinfunction "QG_6") (pintype "tri_state"))
    )
    (net (code "121") (name "Net-(U13-IN8)") (class "Default")
      (node (ref "U13") (pin "8") (pinfunction "IN8_8") (pintype "passive"))
      (node (ref "U7") (pin "7") (pinfunction "QH_7") (pintype "tri_state"))
    )
    (net (code "122") (name "Net-(U14-IN8)") (class "Default")
      (node (ref "R3") (pin "1") (pinfunction "1_1") (pintype "passive"))
      (node (ref "U14") (pin "8") (pinfunction "IN8_8") (pintype "passive"))
    )
    (net (code "123") (name "PGND") (class "Default")
      (node (ref "C1") (pin "N") (pinfunction "-_N") (pintype "passive"))
      (node (ref "C10") (pin "2") (pinfunction "-_2") (pintype "passive"))
      (node (ref "C11") (pin "2") (pinfunction "-_2") (pintype "passive"))
      (node (ref "C12") (pin "2") (pinfunction "-_2") (pintype "passive"))
      (node (ref "C2") (pin "N") (pinfunction "-_N") (pintype "passive"))
      (node (ref "C3") (pin "N") (pinfunction "-_N") (pintype "passive"))
      (node (ref "C4") (pin "2") (pinfunction "-_2") (pintype "passive"))
      (node (ref "C5") (pin "2") (pinfunction "-_2") (pintype "passive"))
      (node (ref "C6") (pin "2") (pinfunction "-_2") (pintype "passive"))
      (node (ref "C7") (pin "2") (pinfunction "-_2") (pintype "passive"))
      (node (ref "C8") (pin "2") (pinfunction "-_2") (pintype "passive"))
      (node (ref "C9") (pin "2") (pinfunction "-_2") (pintype "passive"))
      (node (ref "CONFIG0") (pin "2") (pinfunction "2_2") (pintype "passive"))
      (node (ref "CONFIG1") (pin "1") (pinfunction "1_1") (pintype "passive"))
      (node (ref "J1") (pin "41") (pinfunction "41_41") (pintype "power_in"))
      (node (ref "J1") (pin "54") (pinfunction "54_54") (pintype "power_in"))
      (node (ref "J1") (pin "55") (pinfunction "55_55") (pintype "power_in"))
      (node (ref "J1") (pin "56") (pinfunction "56_56") (pintype "power_in"))
      (node (ref "J1") (pin "57") (pinfunction "57_57") (pintype "power_in"))
      (node (ref "J1") (pin "58") (pinfunction "58_58") (pintype "power_in"))
      (node (ref "J1") (pin "59") (pinfunction "59_59") (pintype "power_in"))
      (node (ref "J1") (pin "60") (pinfunction "60_60") (pintype "power_in"))
      (node (ref "J2") (pin "10") (pinfunction "10_10") (pintype "power_in"))
      (node (ref "J2") (pin "11") (pinfunction "11_11") (pintype "power_in"))
      (node (ref "J2") (pin "12") (pinfunction "12_12") (pintype "power_in"))
      (node (ref "J2") (pin "20") (pinfunction "20_20") (pintype "power_in"))
      (node (ref "J2") (pin "21") (pinfunction "21_21") (pintype "power_in"))
      (node (ref "J2") (pin "22") (pinfunction "22_22") (pintype "power_in"))
      (node (ref "J2") (pin "25") (pinfunction "25_25") (pintype "power_in"))
      (node (ref "J2") (pin "26") (pinfunction "26_26") (pintype "power_in"))
      (node (ref "J2") (pin "7") (pinfunction "7_7") (pintype "power_in"))
      (node (ref "J2") (pin "8") (pinfunction "8_8") (pintype "power_in"))
      (node (ref "J2") (pin "9") (pinfunction "9_9") (pintype "power_in"))
      (node (ref "J3") (pin "10") (pinfunction "10_10") (pintype "power_in"))
      (node (ref "J3") (pin "11") (pinfunction "11_11") (pintype "power_in"))
      (node (ref "J3") (pin "12") (pinfunction "12_12") (pintype "power_in"))
      (node (ref "J3") (pin "20") (pinfunction "20_20") (pintype "power_in"))
      (node (ref "J3") (pin "21") (pinfunction "21_21") (pintype "power_in"))
      (node (ref "J3") (pin "22") (pinfunction "22_22") (pintype "power_in"))
      (node (ref "J3") (pin "25") (pinfunction "25_25") (pintype "power_in"))
      (node (ref "J3") (pin "26") (pinfunction "26_26") (pintype "power_in"))
      (node (ref "J3") (pin "7") (pinfunction "7_7") (pintype "power_in"))
      (node (ref "J3") (pin "8") (pinfunction "8_8") (pintype "power_in"))
      (node (ref "J3") (pin "9") (pinfunction "9_9") (pintype "power_in"))
      (node (ref "J4") (pin "2") (pinfunction "2_2") (pintype "passive"))
      (node (ref "R3") (pin "2") (pinfunction "2_2") (pintype "passive"))
      (node (ref "U1") (pin "13") (pinfunction "~{OE}_13") (pintype "input"))
      (node (ref "U1") (pin "8") (pinfunction "GND_8") (pintype "power_in"))
      (node (ref "U10") (pin "9") (pinfunction "GND_9") (pintype "passive"))
      (node (ref "U11") (pin "10") (pinfunction "COM_10") (pintype "passive"))
      (node (ref "U12") (pin "9") (pinfunction "GND_9") (pintype "passive"))
      (node (ref "U13") (pin "10") (pinfunction "COM_10") (pintype "passive"))
      (node (ref "U14") (pin "10") (pinfunction "COM_10") (pintype "passive"))
      (node (ref "U15") (pin "2") (pinfunction "GND_2") (pintype "passive"))
      (node (ref "U2") (pin "13") (pinfunction "~{OE}_13") (pintype "input"))
      (node (ref "U2") (pin "8") (pinfunction "GND_8") (pintype "power_in"))
      (node (ref "U3") (pin "21") (pinfunction "GND_21") (pintype "power_in"))
      (node (ref "U3") (pin "3") (pinfunction "GND_3") (pintype "power_in"))
      (node (ref "U3") (pin "5") (pinfunction "GND_5") (pintype "power_in"))
      (node (ref "U4") (pin "13") (pinfunction "~{OE}_13") (pintype "input"))
      (node (ref "U4") (pin "8") (pinfunction "GND_8") (pintype "power_in"))
      (node (ref "U5") (pin "13") (pinfunction "~{OE}_13") (pintype "input"))
      (node (ref "U5") (pin "8") (pinfunction "GND_8") (pintype "power_in"))
      (node (ref "U6") (pin "13") (pinfunction "~{OE}_13") (pintype "input"))
      (node (ref "U6") (pin "8") (pinfunction "GND_8") (pintype "power_in"))
      (node (ref "U7") (pin "13") (pinfunction "~{OE}_13") (pintype "input"))
      (node (ref "U7") (pin "8") (pinfunction "GND_8") (pintype "power_in"))
      (node (ref "U8") (pin "9") (pinfunction "GND_9") (pintype "passive"))
      (node (ref "U9") (pin "10") (pinfunction "COM_10") (pintype "passive"))
      (node (ref "ZD1") (pin "1") (pinfunction "A_1") (pintype "passive"))
      (node (ref "ZD2") (pin "1") (pinfunction "A_1") (pintype "passive"))
      (node (ref "ZD3") (pin "1") (pinfunction "A_1") (pintype "passive"))
      (node (ref "ZD4") (pin "1") (pinfunction "A_1") (pintype "passive"))
      (node (ref "ZD5") (pin "1") (pinfunction "A_1") (pintype "passive"))
      (node (ref "ZD6") (pin "1") (pinfunction "A_1") (pintype "passive"))
      (node (ref "ZD7") (pin "1") (pinfunction "A_1") (pintype "passive"))
    )
    (net (code "124") (name "PVCC") (class "Default")
      (node (ref "C1") (pin "P") (pinfunction "+_P") (pintype "passive"))
      (node (ref "C3") (pin "P") (pinfunction "+_P") (pintype "passive"))
      (node (ref "J1") (pin "42") (pinfunction "42_42") (pintype "power_in"))
      (node (ref "J1") (pin "43") (pinfunction "43_43") (pintype "power_in"))
      (node (ref "J2") (pin "1") (pinfunction "1_1") (pintype "power_in"))
      (node (ref "J2") (pin "2") (pinfunction "2_2") (pintype "power_in"))
      (node (ref "J2") (pin "3") (pinfunction "3_3") (pintype "power_in"))
      (node (ref "J2") (pin "4") (pinfunction "4_4") (pintype "power_in"))
      (node (ref "J2") (pin "5") (pinfunction "5_5") (pintype "power_in"))
      (node (ref "J2") (pin "6") (pinfunction "6_6") (pintype "power_in"))
      (node (ref "J3") (pin "1") (pinfunction "1_1") (pintype "power_in"))
      (node (ref "J3") (pin "2") (pinfunction "2_2") (pintype "power_in"))
      (node (ref "J3") (pin "3") (pinfunction "3_3") (pintype "power_in"))
      (node (ref "J3") (pin "4") (pinfunction "4_4") (pintype "power_in"))
      (node (ref "J3") (pin "5") (pinfunction "5_5") (pintype "power_in"))
      (node (ref "J3") (pin "6") (pinfunction "6_6") (pintype "power_in"))
      (node (ref "J4") (pin "1") (pinfunction "1_1") (pintype "passive"))
      (node (ref "U10") (pin "10") (pinfunction "COM_10") (pintype "passive"))
      (node (ref "U11") (pin "9") (pinfunction "VCC_9") (pintype "passive"))
      (node (ref "U12") (pin "10") (pinfunction "COM_10") (pintype "passive"))
      (node (ref "U13") (pin "9") (pinfunction "VCC_9") (pintype "passive"))
      (node (ref "U14") (pin "9") (pinfunction "VCC_9") (pintype "passive"))
      (node (ref "U15") (pin "1") (pinfunction "IN_1") (pintype "passive"))
      (node (ref "U8") (pin "10") (pinfunction "COM_10") (pintype "passive"))
      (node (ref "U9") (pin "9") (pinfunction "VCC_9") (pintype "passive"))
    )
    (net (code "125") (name "unconnected-(J1-Pad46)") (class "Default")
      (node (ref "J1") (pin "46") (pinfunction "46_46") (pintype "power_in+no_connect"))
    )
    (net (code "126") (name "unconnected-(U3-ADC6-Pad19)") (class "Default")
      (node (ref "U3") (pin "19") (pinfunction "ADC6_19") (pintype "input+no_connect"))
    )
    (net (code "127") (name "unconnected-(U3-ADC7-Pad22)") (class "Default")
      (node (ref "U3") (pin "22") (pinfunction "ADC7_22") (pintype "input+no_connect"))
    )
    (net (code "128") (name "unconnected-(U3-PC6_(~{RESET})-Pad29)") (class "Default")
      (node (ref "U3") (pin "29") (pinfunction "PC6_(~{RESET})_29") (pintype "bidirectional"))
    )
    (net (code "129") (name "unconnected-(U3-PD1_(TXD)-Pad31)") (class "Default")
      (node (ref "U3") (pin "31") (pinfunction "PD1_(TXD)_31") (pintype "bidirectional+no_connect"))
    )
    (net (code "130") (name "unconnected-(U3-PD3_(INT1)-Pad1)") (class "Default")
      (node (ref "U3") (pin "1") (pinfunction "PD3_(INT1)_1") (pintype "bidirectional+no_connect"))
    )
    (net (code "131") (name "unconnected-(U3-PD5_(T1)-Pad9)") (class "Default")
      (node (ref "U3") (pin "9") (pinfunction "PD5_(T1)_9") (pintype "bidirectional+no_connect"))
    )
    (net (code "132") (name "unconnected-(U3-PD7_(AIN1)-Pad11)") (class "Default")
      (node (ref "U3") (pin "11") (pinfunction "PD7_(AIN1)_11") (pintype "bidirectional+no_connect"))
    )
    (net (code "133") (name "unconnected-(U6-QH'-Pad9)") (class "Default")
      (node (ref "U6") (pin "9") (pinfunction "QH'_9") (pintype "output+no_connect"))
    )
    (net (code "134") (name "unconnected-(U12-OUT5-Pad14)") (class "Default")
      (node (ref "U12") (pin "14") (pinfunction "OUT5_14") (pintype "passive"))
    )
    (net (code "135") (name "unconnected-(U12-OUT6-Pad13)") (class "Default")
      (node (ref "U12") (pin "13") (pinfunction "OUT6_13") (pintype "passive"))
    )
    (net (code "136") (name "unconnected-(U12-OUT7-Pad12)") (class "Default")
      (node (ref "U12") (pin "12") (pinfunction "OUT7_12") (pintype "passive"))
    )
    (net (code "137") (name "unconnected-(U12-OUT8-Pad11)") (class "Default")
      (node (ref "U12") (pin "11") (pinfunction "OUT8_11") (pintype "passive"))
    )
    (net (code "138") (name "unconnected-(U13-OUT5-Pad14)") (class "Default")
      (node (ref "U13") (pin "14") (pinfunction "OUT5_14") (pintype "passive"))
    )
    (net (code "139") (name "unconnected-(U13-OUT6-Pad13)") (class "Default")
      (node (ref "U13") (pin "13") (pinfunction "OUT6_13") (pintype "passive"))
    )
    (net (code "140") (name "unconnected-(U13-OUT7-Pad12)") (class "Default")
      (node (ref "U13") (pin "12") (pinfunction "OUT7_12") (pintype "passive"))
    )
    (net (code "141") (name "unconnected-(U13-OUT8-Pad11)") (class "Default")
      (node (ref "U13") (pin "11") (pinfunction "OUT8_11") (pintype "passive"))
    )
    (net (code "142") (name "unconnected-(U14-OUT8-Pad11)") (class "Default")
      (node (ref "U14") (pin "11") (pinfunction "OUT8_11") (pintype "passive+no_connect"))
    )
  )
)
